# TSSOP-8_Adaptor.net
KiCad netlist of a schematic drawn in Altium Designer
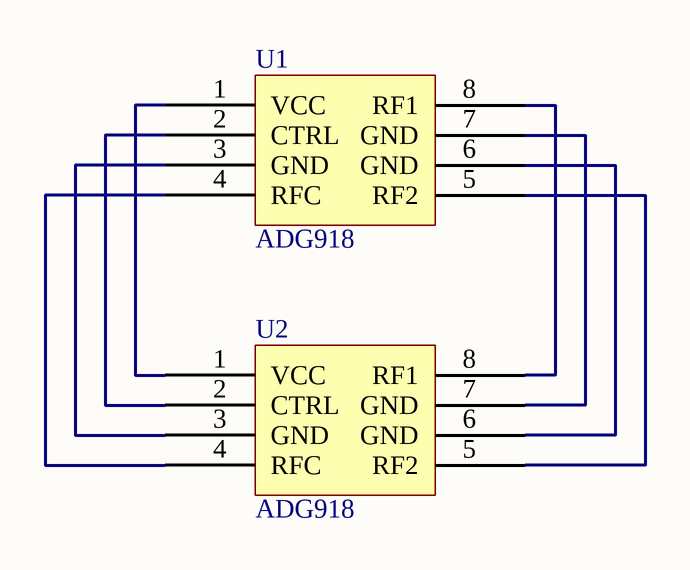
[diagram p0: TSSOP-8 Adaptor.SCHDOC]

(export (version "E")
  (design (tool "Eeschema 10.0.6"))
  (components
    (comp (ref "U1") (value "ADG918") (footprint "SSO-G8/P.65") (libsource (lib "2005Parts") (part "ADG918")))
    (comp (ref "U2") (value "ADG918") (footprint "dip-8") (libsource (lib "2005Parts") (part "ADG918")))
  )
  (nets
    (net (code "1") (name "Net-(U1-CTRL)") (class "Default")
      (node (ref "U1") (pin "2") (pinfunction "CTRL_2") (pintype "passive"))
      (node (ref "U2") (pin "2") (pinfunction "CTRL_2") (pintype "passive"))
    )
    (net (code "2") (name "Net-(U1-GND-Pad3)") (class "Default")
      (node (ref "U1") (pin "3") (pinfunction "GND_3") (pintype "passive"))
      (node (ref "U2") (pin "3") (pinfunction "GND_3") (pintype "passive"))
    )
    (net (code "3") (name "Net-(U1-GND-Pad6)") (class "Default")
      (node (ref "U1") (pin "6") (pinfunction "GND_6") (pintype "passive"))
      (node (ref "U2") (pin "6") (pinfunction "GND_6") (pintype "passive"))
    )
    (net (code "4") (name "Net-(U1-GND-Pad7)") (class "Default")
      (node (ref "U1") (pin "7") (pinfunction "GND_7") (pintype "passive"))
      (node (ref "U2") (pin "7") (pinfunction "GND_7") (pintype "passive"))
    )
    (net (code "5") (name "Net-(U1-RF1)") (class "Default")
      (node (ref "U1") (pin "8") (pinfunction "RF1_8") (pintype "passive"))
      (node (ref "U2") (pin "8") (pinfunction "RF1_8") (pintype "passive"))
    )
    (net (code "6") (name "Net-(U1-RF2)") (class "Default")
      (node (ref "U1") (pin "5") (pinfunction "RF2_5") (pintype "passive"))
      (node (ref "U2") (pin "5") (pinfunction "RF2_5") (pintype "passive"))
    )
    (net (code "7") (name "Net-(U1-RFC)") (class "Default")
      (node (ref "U1") (pin "4") (pinfunction "RFC_4") (pintype "passive"))
      (node (ref "U2") (pin "4") (pinfunction "RFC_4") (pintype "passive"))
    )
    (net (code "8") (name "Net-(U1-VCC)") (class "Default")
      (node (ref "U1") (pin "1") (pinfunction "VCC_1") (pintype "passive"))
      (node (ref "U2") (pin "1") (pinfunction "VCC_1") (pintype "passive"))
    )
  )
)
